# Sheet1.net
KiCad netlist of a schematic drawn in Altium Designer
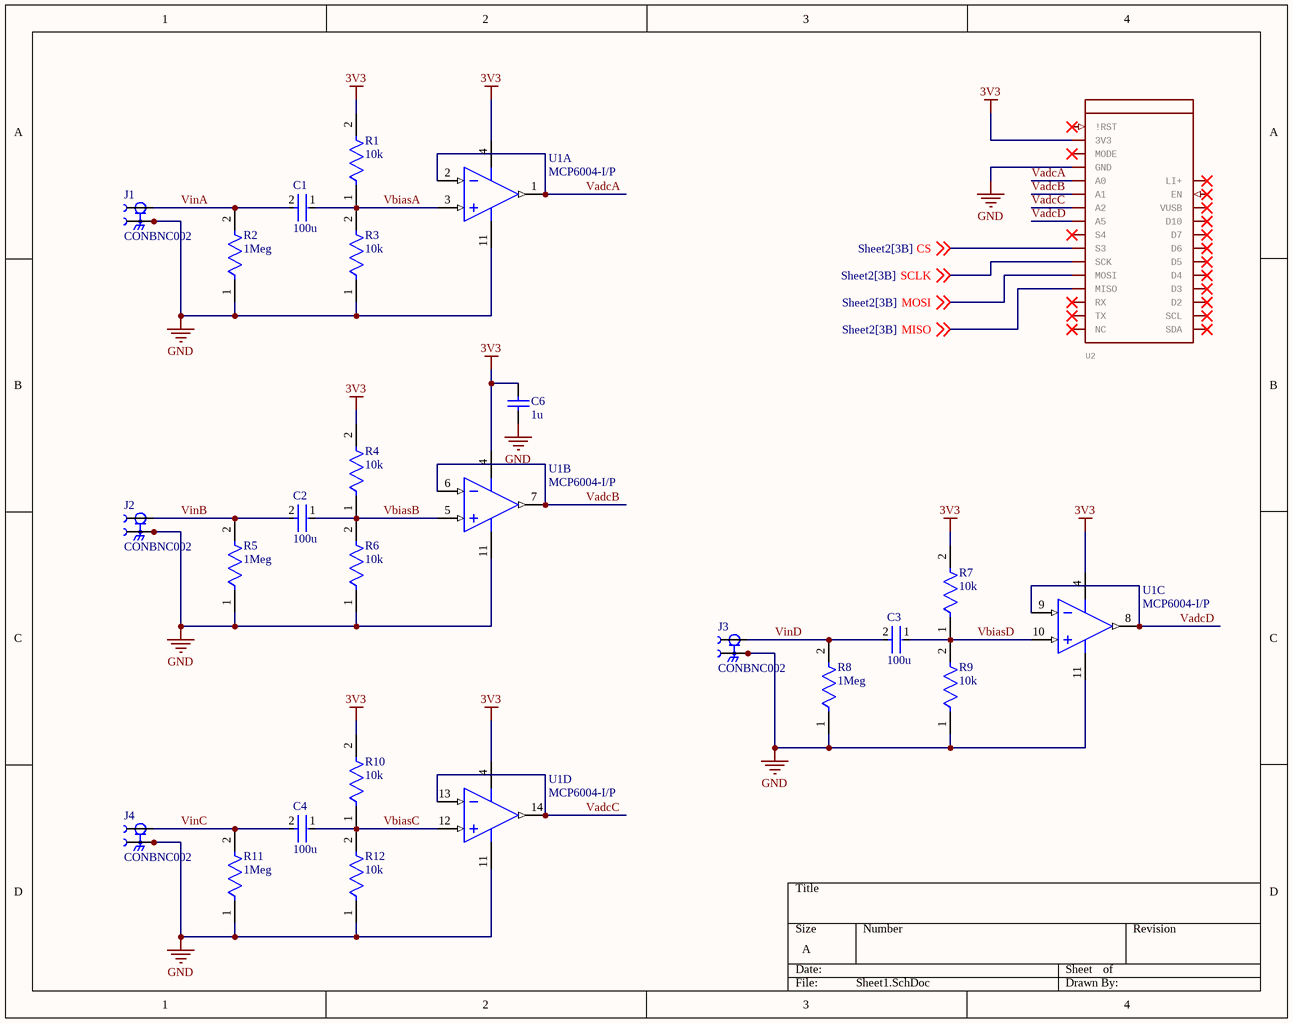
[diagram p0: Sheet1.SchDoc]

(export (version "E")
  (design (tool "Eeschema 10.0.6"))
  (components
    (comp (ref "C1")
      (value "100u")
      (footprint "FP-GRM31C-0_3-e0_3_0_8-IPC_C")
      (description "Chip Multilayer Ceramic Capacitors for General Purpose, 1206, 100uF, X6T, +22%/-33%, 20%, 6.3V")
      (libsource (lib "Altium Content Vault") (part "f23184f103b6ebe33a8c269c53dcba6"))
    )
    (comp (ref "C2")
      (value "100u")
      (footprint "FP-GRM31C-0_3-e0_3_0_8-IPC_C")
      (description "Chip Multilayer Ceramic Capacitors for General Purpose, 1206, 100uF, X6T, +22%/-33%, 20%, 6.3V")
      (libsource (lib "Altium Content Vault") (part "f23184f103b6ebe33a8c269c53dcba6"))
    )
    (comp (ref "C3")
      (value "100u")
      (footprint "FP-GRM31C-0_3-e0_3_0_8-IPC_C")
      (description "Chip Multilayer Ceramic Capacitors for General Purpose, 1206, 100uF, X6T, +22%/-33%, 20%, 6.3V")
      (libsource (lib "Altium Content Vault") (part "f23184f103b6ebe33a8c269c53dcba6"))
    )
    (comp (ref "C4")
      (value "100u")
      (footprint "FP-GRM31C-0_3-e0_3_0_8-IPC_C")
      (description "Chip Multilayer Ceramic Capacitors for General Purpose, 1206, 100uF, X6T, +22%/-33%, 20%, 6.3V")
      (libsource (lib "Altium Content Vault") (part "f23184f103b6ebe33a8c269c53dcba6"))
    )
    (comp (ref "C6")
      (value "1u")
      (footprint "CAPC3216X110X50LL20T25")
      (description "Chip Capacitor, 1 uF, +/- 10%, 50 V, -55 to 125 degC, 1206 (3216 Metric), RoHS, Tape and Reel")
      (fields (field (name "MANUFACTURER") "Kemet") (field (name "TOLERANCE") "10%"))
      (libsource (lib "Altium Content Vault") (part "CAP-NP-2"))
    )
    (comp (ref "J1")
      (value "CONBNC002")
      (footprint "LINX_CONBNC002")
      (description "BNC Jack 50 Ohm PCB Through Hole")
      (fields (field (name "MF") "Linx Technologies Inc."))
      (libsource (lib "CONBNC002") (part "CONBNC002"))
    )
    (comp (ref "J2")
      (value "CONBNC002")
      (footprint "LINX_CONBNC002")
      (description "BNC Jack 50 Ohm PCB Through Hole")
      (fields (field (name "MF") "Linx Technologies Inc."))
      (libsource (lib "CONBNC002") (part "CONBNC002"))
    )
    (comp (ref "J3")
      (value "CONBNC002")
      (footprint "LINX_CONBNC002")
      (description "BNC Jack 50 Ohm PCB Through Hole")
      (fields (field (name "MF") "Linx Technologies Inc."))
      (libsource (lib "CONBNC002") (part "CONBNC002"))
    )
    (comp (ref "J4")
      (value "CONBNC002")
      (footprint "LINX_CONBNC002")
      (description "BNC Jack 50 Ohm PCB Through Hole")
      (fields (field (name "MF") "Linx Technologies Inc."))
      (libsource (lib "CONBNC002") (part "CONBNC002"))
    )
    (comp (ref "R1")
      (value "10k")
      (footprint "FP-CR1206-IPC_B")
      (description "Thick Film Chip Resistors 1206 10kΩ 0.25W 5% 200ppm/°C")
      (fields (field (name "TOLERANCE") "5%"))
      (libsource (lib "Altium Content Vault") (part "1029c3af85768c4190bb7ad29bc67b5"))
    )
    (comp (ref "R2")
      (value "1Meg")
      (footprint "FP-CRCW1206-e3-MFG")
      (description "RES Thick Film, 1MΩ, 1%, 0.25W, 100ppm/°C, 1206")
      (fields (field (name "TOLERANCE") "1%"))
      (libsource (lib "Altium Content Vault") (part "1029c3af85768c4190bb7ad29bc67b5"))
    )
    (comp (ref "R3")
      (value "10k")
      (footprint "FP-CR1206-IPC_B")
      (description "Thick Film Chip Resistors 1206 10kΩ 0.25W 5% 200ppm/°C")
      (fields (field (name "TOLERANCE") "5%"))
      (libsource (lib "Altium Content Vault") (part "1029c3af85768c4190bb7ad29bc67b5"))
    )
    (comp (ref "R4")
      (value "10k")
      (footprint "FP-CR1206-IPC_B")
      (description "Thick Film Chip Resistors 1206 10kΩ 0.25W 5% 200ppm/°C")
      (fields (field (name "TOLERANCE") "5%"))
      (libsource (lib "Altium Content Vault") (part "1029c3af85768c4190bb7ad29bc67b5"))
    )
    (comp (ref "R5")
      (value "1Meg")
      (footprint "FP-CRCW1206-e3-MFG")
      (description "RES Thick Film, 1MΩ, 1%, 0.25W, 100ppm/°C, 1206")
      (fields (field (name "TOLERANCE") "1%"))
      (libsource (lib "Altium Content Vault") (part "1029c3af85768c4190bb7ad29bc67b5"))
    )
    (comp (ref "R6")
      (value "10k")
      (footprint "FP-CR1206-IPC_B")
      (description "Thick Film Chip Resistors 1206 10kΩ 0.25W 5% 200ppm/°C")
      (fields (field (name "TOLERANCE") "5%"))
      (libsource (lib "Altium Content Vault") (part "1029c3af85768c4190bb7ad29bc67b5"))
    )
    (comp (ref "R7")
      (value "10k")
      (footprint "FP-CR1206-IPC_B")
      (description "Thick Film Chip Resistors 1206 10kΩ 0.25W 5% 200ppm/°C")
      (fields (field (name "TOLERANCE") "5%"))
      (libsource (lib "Altium Content Vault") (part "1029c3af85768c4190bb7ad29bc67b5"))
    )
    (comp (ref "R8")
      (value "1Meg")
      (footprint "FP-CRCW1206-e3-MFG")
      (description "RES Thick Film, 1MΩ, 1%, 0.25W, 100ppm/°C, 1206")
      (fields (field (name "TOLERANCE") "1%"))
      (libsource (lib "Altium Content Vault") (part "1029c3af85768c4190bb7ad29bc67b5"))
    )
    (comp (ref "R9")
      (value "10k")
      (footprint "FP-CR1206-IPC_B")
      (description "Thick Film Chip Resistors 1206 10kΩ 0.25W 5% 200ppm/°C")
      (fields (field (name "TOLERANCE") "5%"))
      (libsource (lib "Altium Content Vault") (part "1029c3af85768c4190bb7ad29bc67b5"))
    )
    (comp (ref "R10")
      (value "10k")
      (footprint "FP-CR1206-IPC_B")
      (description "Thick Film Chip Resistors 1206 10kΩ 0.25W 5% 200ppm/°C")
      (fields (field (name "TOLERANCE") "5%"))
      (libsource (lib "Altium Content Vault") (part "1029c3af85768c4190bb7ad29bc67b5"))
    )
    (comp (ref "R11")
      (value "1Meg")
      (footprint "FP-CRCW1206-e3-MFG")
      (description "RES Thick Film, 1MΩ, 1%, 0.25W, 100ppm/°C, 1206")
      (fields (field (name "TOLERANCE") "1%"))
      (libsource (lib "Altium Content Vault") (part "1029c3af85768c4190bb7ad29bc67b5"))
    )
    (comp (ref "R12")
      (value "10k")
      (footprint "FP-CR1206-IPC_B")
      (description "Thick Film Chip Resistors 1206 10kΩ 0.25W 5% 200ppm/°C")
      (fields (field (name "TOLERANCE") "5%"))
      (libsource (lib "Altium Content Vault") (part "1029c3af85768c4190bb7ad29bc67b5"))
    )
    (comp (ref "U1")
      (value "MCP6004-I/P")
      (footprint "PDIP300-P14")
      (description "None")
      (libsource (lib "Altium Content Vault") (part "AMP-OPA-MCP6004-IL14"))
    )
    (comp (ref "U2")
      (value "Particle Photon 2 Wi-Fi enabled development kit   Footprint and formfactor based on Adafruit Feather.")
      (footprint "PHOTON2")
      (libsource (lib "Particle-Devices.Library") (part "PHOTON2"))
    )
  )
  (nets
    (net (code "1") (name "/VadcA") (class "Default")
      (node (ref "U1") (pin "1") (pinfunction "VOUTA_1") (pintype "output"))
      (node (ref "U1") (pin "2") (pinfunction "VINA-_2") (pintype "input"))
      (node (ref "U2") (pin "5") (pinfunction "A0_5") (pintype "bidirectional"))
    )
    (net (code "2") (name "/VadcB") (class "Default")
      (node (ref "U1") (pin "6") (pinfunction "VINB-_6") (pintype "input"))
      (node (ref "U1") (pin "7") (pinfunction "VOUTB_7") (pintype "output"))
      (node (ref "U2") (pin "6") (pinfunction "A1_6") (pintype "bidirectional"))
    )
    (net (code "3") (name "/VadcC") (class "Default")
      (node (ref "U1") (pin "13") (pinfunction "VIND-_13") (pintype "input"))
      (node (ref "U1") (pin "14") (pinfunction "VOUTD_14") (pintype "output"))
      (node (ref "U2") (pin "7") (pinfunction "A2_7") (pintype "bidirectional"))
    )
    (net (code "4") (name "/VadcD") (class "Default")
      (node (ref "U1") (pin "8") (pinfunction "VOUTC_8") (pintype "output"))
      (node (ref "U1") (pin "9") (pinfunction "VINC-_9") (pintype "input"))
      (node (ref "U2") (pin "8") (pinfunction "A5_8") (pintype "bidirectional"))
    )
    (net (code "5") (name "/VbiasA") (class "Default")
      (node (ref "C1") (pin "1") (pinfunction "1_1") (pintype "passive"))
      (node (ref "R1") (pin "1") (pinfunction "1_1") (pintype "passive"))
      (node (ref "R3") (pin "2") (pinfunction "2_2") (pintype "passive"))
      (node (ref "U1") (pin "3") (pinfunction "VINA+_3") (pintype "input"))
    )
    (net (code "6") (name "/VbiasB") (class "Default")
      (node (ref "C2") (pin "1") (pinfunction "1_1") (pintype "passive"))
      (node (ref "R4") (pin "1") (pinfunction "1_1") (pintype "passive"))
      (node (ref "R6") (pin "2") (pinfunction "2_2") (pintype "passive"))
      (node (ref "U1") (pin "5") (pinfunction "VINB+_5") (pintype "input"))
    )
    (net (code "7") (name "/VbiasC") (class "Default")
      (node (ref "C4") (pin "1") (pinfunction "1_1") (pintype "passive"))
      (node (ref "R10") (pin "1") (pinfunction "1_1") (pintype "passive"))
      (node (ref "R12") (pin "2") (pinfunction "2_2") (pintype "passive"))
      (node (ref "U1") (pin "12") (pinfunction "VIND+_12") (pintype "input"))
    )
    (net (code "8") (name "/VbiasD") (class "Default")
      (node (ref "C3") (pin "1") (pinfunction "1_1") (pintype "passive"))
      (node (ref "R7") (pin "1") (pinfunction "1_1") (pintype "passive"))
      (node (ref "R9") (pin "2") (pinfunction "2_2") (pintype "passive"))
      (node (ref "U1") (pin "10") (pinfunction "VINC+_10") (pintype "input"))
    )
    (net (code "9") (name "/VinA") (class "Default")
      (node (ref "C1") (pin "2") (pinfunction "2_2") (pintype "passive"))
      (node (ref "J1") (pin "1") (pinfunction "1_1") (pintype "passive"))
      (node (ref "R2") (pin "2") (pinfunction "2_2") (pintype "passive"))
    )
    (net (code "10") (name "/VinB") (class "Default")
      (node (ref "C2") (pin "2") (pinfunction "2_2") (pintype "passive"))
      (node (ref "J2") (pin "1") (pinfunction "1_1") (pintype "passive"))
      (node (ref "R5") (pin "2") (pinfunction "2_2") (pintype "passive"))
    )
    (net (code "11") (name "/VinC") (class "Default")
      (node (ref "C4") (pin "2") (pinfunction "2_2") (pintype "passive"))
      (node (ref "J4") (pin "1") (pinfunction "1_1") (pintype "passive"))
      (node (ref "R11") (pin "2") (pinfunction "2_2") (pintype "passive"))
    )
    (net (code "12") (name "/VinD") (class "Default")
      (node (ref "C3") (pin "2") (pinfunction "2_2") (pintype "passive"))
      (node (ref "J3") (pin "1") (pinfunction "1_1") (pintype "passive"))
      (node (ref "R8") (pin "2") (pinfunction "2_2") (pintype "passive"))
    )
    (net (code "13") (name "3V3") (class "Default")
      (node (ref "C6") (pin "2") (pinfunction "2_2") (pintype "passive"))
      (node (ref "R1") (pin "2") (pinfunction "2_2") (pintype "passive"))
      (node (ref "R10") (pin "2") (pinfunction "2_2") (pintype "passive"))
      (node (ref "R4") (pin "2") (pinfunction "2_2") (pintype "passive"))
      (node (ref "R7") (pin "2") (pinfunction "2_2") (pintype "passive"))
      (node (ref "U1") (pin "4") (pinfunction "VDD_4") (pintype "power_in"))
      (node (ref "U2") (pin "2") (pinfunction "3V3_2") (pintype "power_in"))
    )
    (net (code "14") (name "CS") (class "Default")
      (node (ref "U2") (pin "10") (pinfunction "S3_10") (pintype "bidirectional"))
    )
    (net (code "15") (name "GND") (class "Default")
      (node (ref "C6") (pin "1") (pinfunction "1_1") (pintype "passive"))
      (node (ref "J1") (pin "2") (pinfunction "2_2") (pintype "passive"))
      (node (ref "J1") (pin "S1") (pinfunction "2_S1") (pintype "passive"))
      (node (ref "J1") (pin "S2") (pinfunction "2_S2") (pintype "passive"))
      (node (ref "J2") (pin "2") (pinfunction "2_2") (pintype "passive"))
      (node (ref "J2") (pin "S1") (pinfunction "2_S1") (pintype "passive"))
      (node (ref "J2") (pin "S2") (pinfunction "2_S2") (pintype "passive"))
      (node (ref "J3") (pin "2") (pinfunction "2_2") (pintype "passive"))
      (node (ref "J3") (pin "S1") (pinfunction "2_S1") (pintype "passive"))
      (node (ref "J3") (pin "S2") (pinfunction "2_S2") (pintype "passive"))
      (node (ref "J4") (pin "2") (pinfunction "2_2") (pintype "passive"))
      (node (ref "J4") (pin "S1") (pinfunction "2_S1") (pintype "passive"))
      (node (ref "J4") (pin "S2") (pinfunction "2_S2") (pintype "passive"))
      (node (ref "R11") (pin "1") (pinfunction "1_1") (pintype "passive"))
      (node (ref "R12") (pin "1") (pinfunction "1_1") (pintype "passive"))
      (node (ref "R2") (pin "1") (pinfunction "1_1") (pintype "passive"))
      (node (ref "R3") (pin "1") (pinfunction "1_1") (pintype "passive"))
      (node (ref "R5") (pin "1") (pinfunction "1_1") (pintype "passive"))
      (node (ref "R6") (pin "1") (pinfunction "1_1") (pintype "passive"))
      (node (ref "R8") (pin "1") (pinfunction "1_1") (pintype "passive"))
      (node (ref "R9") (pin "1") (pinfunction "1_1") (pintype "passive"))
      (node (ref "U1") (pin "11") (pinfunction "VSS_11") (pintype "power_in"))
      (node (ref "U2") (pin "4") (pinfunction "GND_4") (pintype "power_in"))
    )
    (net (code "16") (name "MISO") (class "Default")
      (node (ref "U2") (pin "13") (pinfunction "MISO_13") (pintype "bidirectional"))
    )
    (net (code "17") (name "MOSI") (class "Default")
      (node (ref "U2") (pin "12") (pinfunction "MOSI_12") (pintype "bidirectional"))
    )
    (net (code "18") (name "SCLK") (class "Default")
      (node (ref "U2") (pin "11") (pinfunction "SCK_11") (pintype "bidirectional"))
    )
    (net (code "19") (name "unconnected-(U2-!RST-Pad1)") (class "Default")
      (node (ref "U2") (pin "1") (pinfunction "!RST_1") (pintype "input+no_connect"))
    )
    (net (code "20") (name "unconnected-(U2-D2-Pad19)") (class "Default")
      (node (ref "U2") (pin "19") (pinfunction "D2_19") (pintype "bidirectional+no_connect"))
    )
    (net (code "21") (name "unconnected-(U2-D3-Pad20)") (class "Default")
      (node (ref "U2") (pin "20") (pinfunction "D3_20") (pintype "bidirectional+no_connect"))
    )
    (net (code "22") (name "unconnected-(U2-D4-Pad21)") (class "Default")
      (node (ref "U2") (pin "21") (pinfunction "D4_21") (pintype "bidirectional+no_connect"))
    )
    (net (code "23") (name "unconnected-(U2-D5-Pad22)") (class "Default")
      (node (ref "U2") (pin "22") (pinfunction "D5_22") (pintype "bidirectional+no_connect"))
    )
    (net (code "24") (name "unconnected-(U2-D6-Pad23)") (class "Default")
      (node (ref "U2") (pin "23") (pinfunction "D6_23") (pintype "bidirectional+no_connect"))
    )
    (net (code "25") (name "unconnected-(U2-D7-Pad24)") (class "Default")
      (node (ref "U2") (pin "24") (pinfunction "D7_24") (pintype "bidirectional+no_connect"))
    )
    (net (code "26") (name "unconnected-(U2-D10-Pad25)") (class "Default")
      (node (ref "U2") (pin "25") (pinfunction "D10_25") (pintype "bidirectional+no_connect"))
    )
    (net (code "27") (name "unconnected-(U2-EN-Pad27)") (class "Default")
      (node (ref "U2") (pin "27") (pinfunction "EN_27") (pintype "input+no_connect"))
    )
    (net (code "28") (name "unconnected-(U2-LI+-Pad28)") (class "Default")
      (node (ref "U2") (pin "28") (pinfunction "LI+_28") (pintype "power_in+no_connect"))
    )
    (net (code "29") (name "unconnected-(U2-MODE-Pad3)") (class "Default")
      (node (ref "U2") (pin "3") (pinfunction "MODE_3") (pintype "bidirectional+no_connect"))
    )
    (net (code "30") (name "unconnected-(U2-NC-Pad16)") (class "Default")
      (node (ref "U2") (pin "16") (pinfunction "NC_16") (pintype "bidirectional+no_connect"))
    )
    (net (code "31") (name "unconnected-(U2-RX-Pad14)") (class "Default")
      (node (ref "U2") (pin "14") (pinfunction "RX_14") (pintype "bidirectional+no_connect"))
    )
    (net (code "32") (name "unconnected-(U2-S4-Pad9)") (class "Default")
      (node (ref "U2") (pin "9") (pinfunction "S4_9") (pintype "bidirectional+no_connect"))
    )
    (net (code "33") (name "unconnected-(U2-SCL-Pad18)") (class "Default")
      (node (ref "U2") (pin "18") (pinfunction "SCL_18") (pintype "bidirectional+no_connect"))
    )
    (net (code "34") (name "unconnected-(U2-SDA-Pad17)") (class "Default")
      (node (ref "U2") (pin "17") (pinfunction "SDA_17") (pintype "bidirectional+no_connect"))
    )
    (net (code "35") (name "unconnected-(U2-TX-Pad15)") (class "Default")
      (node (ref "U2") (pin "15") (pinfunction "TX_15") (pintype "bidirectional+no_connect"))
    )
    (net (code "36") (name "unconnected-(U2-VUSB-Pad26)") (class "Default")
      (node (ref "U2") (pin "26") (pinfunction "VUSB_26") (pintype "power_in+no_connect"))
    )
  )
)
